# Sheet1.net
KiCad netlist of a schematic drawn in Altium Designer
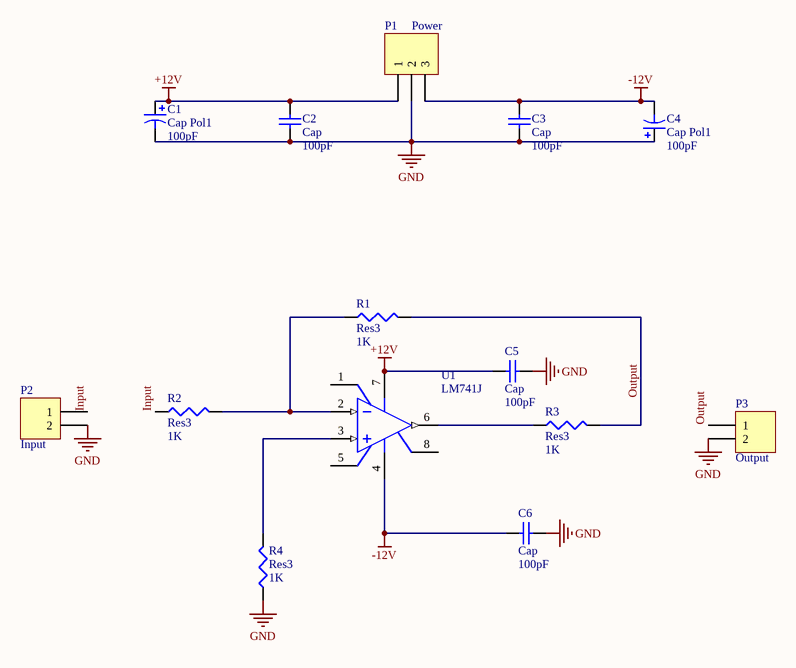
[diagram p0: Sheet1.SchDoc]

(export (version "E")
  (design (tool "Eeschema 10.0.6"))
  (components
    (comp (ref "C1")
      (value "Cap Pol1")
      (footprint "CAPR5-4X5")
      (description "Polarized Capacitor (Radial)")
      (fields (field (name "ALTIUM_VALUE") "100pF") (field (name "PUBLISHER") "Altium Limited"))
      (libsource (lib "Miscellaneous Devices") (part "Cap Pol1"))
    )
    (comp (ref "C2")
      (value "Cap")
      (footprint "CAPR5-4X5")
      (description "Capacitor")
      (fields (field (name "ALTIUM_VALUE") "100pF") (field (name "PUBLISHER") "Altium Limited"))
      (libsource (lib "Miscellaneous Devices") (part "Cap"))
    )
    (comp (ref "C3")
      (value "Cap")
      (footprint "CAPR5-4X5")
      (description "Capacitor")
      (fields (field (name "ALTIUM_VALUE") "100pF") (field (name "PUBLISHER") "Altium Limited"))
      (libsource (lib "Miscellaneous Devices") (part "Cap"))
    )
    (comp (ref "C4")
      (value "Cap Pol1")
      (footprint "CAPR5-4X5")
      (description "Polarized Capacitor (Radial)")
      (fields (field (name "ALTIUM_VALUE") "100pF") (field (name "PUBLISHER") "Altium Limited"))
      (libsource (lib "Miscellaneous Devices") (part "Cap Pol1"))
    )
    (comp (ref "C5")
      (value "Cap")
      (footprint "CAPR5-4X5")
      (description "Capacitor")
      (fields (field (name "ALTIUM_VALUE") "100pF") (field (name "PUBLISHER") "Altium Limited"))
      (libsource (lib "Miscellaneous Devices") (part "Cap"))
    )
    (comp (ref "C6")
      (value "Cap")
      (footprint "CAPR5-4X5")
      (description "Capacitor")
      (fields (field (name "ALTIUM_VALUE") "100pF") (field (name "PUBLISHER") "Altium Limited"))
      (libsource (lib "Miscellaneous Devices") (part "Cap"))
    )
    (comp (ref "P1")
      (value "Power")
      (footprint "HDR1X3")
      (description "Header, 3-Pin")
      (fields (field (name "PUBLISHER") "Altium Limited"))
      (libsource (lib "Miscellaneous Connectors") (part "Header 3"))
    )
    (comp (ref "P2")
      (value "Input")
      (footprint "HDR1X2H")
      (description "Header, 2-Pin, Right Angle")
      (fields (field (name "PUBLISHER") "Altium Limited"))
      (libsource (lib "Miscellaneous Connectors") (part "Header 2H"))
    )
    (comp (ref "P3")
      (value "Output")
      (footprint "HDR1X2")
      (description "Header, 2-Pin")
      (fields (field (name "PUBLISHER") "Altium Limited"))
      (libsource (lib "Miscellaneous Connectors") (part "Header 2"))
    )
    (comp (ref "R1")
      (value "Res3")
      (footprint "J1-0603")
      (description "Resistor")
      (fields (field (name "ALTIUM_VALUE") "1K") (field (name "PUBLISHER") "Altium Limited"))
      (libsource (lib "Miscellaneous Devices") (part "Res3"))
    )
    (comp (ref "R2")
      (value "Res3")
      (footprint "J1-0603")
      (description "Resistor")
      (fields (field (name "ALTIUM_VALUE") "1K") (field (name "PUBLISHER") "Altium Limited"))
      (libsource (lib "Miscellaneous Devices") (part "Res3"))
    )
    (comp (ref "R3")
      (value "Res3")
      (footprint "J1-0603")
      (description "Resistor")
      (fields (field (name "ALTIUM_VALUE") "1K") (field (name "PUBLISHER") "Altium Limited"))
      (libsource (lib "Miscellaneous Devices") (part "Res3"))
    )
    (comp (ref "R4")
      (value "Res3")
      (footprint "J1-0603")
      (description "Resistor")
      (fields (field (name "ALTIUM_VALUE") "1K") (field (name "PUBLISHER") "Altium Limited"))
      (libsource (lib "Miscellaneous Devices") (part "Res3"))
    )
    (comp (ref "U1")
      (value "LM741J")
      (footprint "J08A")
      (description "Operational Amplifier, 8-pin CerDIP")
      (fields (field (name "MANUFACTURER") "National Semiconductor"))
      (libsource (lib "National Semiconductor Amplifier") (part "LM741J"))
    )
  )
  (nets
    (net (code "1") (name "+12V") (class "Default")
      (node (ref "C1") (pin "1") (pinfunction "1_1") (pintype "passive"))
      (node (ref "C2") (pin "2") (pinfunction "2_2") (pintype "passive"))
      (node (ref "C5") (pin "1") (pinfunction "1_1") (pintype "passive"))
      (node (ref "P1") (pin "1") (pinfunction "1_1") (pintype "passive"))
      (node (ref "U1") (pin "7") (pinfunction "V+_7") (pintype "power_in"))
    )
    (net (code "2") (name "-12V") (class "Default")
      (node (ref "C3") (pin "2") (pinfunction "2_2") (pintype "passive"))
      (node (ref "C4") (pin "2") (pinfunction "2_2") (pintype "passive"))
      (node (ref "C6") (pin "1") (pinfunction "1_1") (pintype "passive"))
      (node (ref "P1") (pin "3") (pinfunction "3_3") (pintype "passive"))
      (node (ref "U1") (pin "4") (pinfunction "V-_4") (pintype "power_in"))
    )
    (net (code "3") (name "/Input") (class "Default")
      (node (ref "P2") (pin "1") (pinfunction "1_1") (pintype "passive"))
      (node (ref "R2") (pin "1") (pinfunction "1_1") (pintype "passive"))
    )
    (net (code "4") (name "/Output") (class "Default")
      (node (ref "P3") (pin "1") (pinfunction "1_1") (pintype "passive"))
      (node (ref "R1") (pin "2") (pinfunction "2_2") (pintype "passive"))
      (node (ref "R3") (pin "2") (pinfunction "2_2") (pintype "passive"))
    )
    (net (code "5") (name "GND") (class "Default")
      (node (ref "C1") (pin "2") (pinfunction "2_2") (pintype "passive"))
      (node (ref "C2") (pin "1") (pinfunction "1_1") (pintype "passive"))
      (node (ref "C3") (pin "1") (pinfunction "1_1") (pintype "passive"))
      (node (ref "C4") (pin "1") (pinfunction "1_1") (pintype "passive"))
      (node (ref "C5") (pin "2") (pinfunction "2_2") (pintype "passive"))
      (node (ref "C6") (pin "2") (pinfunction "2_2") (pintype "passive"))
      (node (ref "P1") (pin "2") (pinfunction "2_2") (pintype "passive"))
      (node (ref "P2") (pin "2") (pinfunction "2_2") (pintype "passive"))
      (node (ref "P3") (pin "2") (pinfunction "2_2") (pintype "passive"))
      (node (ref "R4") (pin "1") (pinfunction "1_1") (pintype "passive"))
    )
    (net (code "6") (name "Net-(U1-IN+)") (class "Default")
      (node (ref "R4") (pin "2") (pinfunction "2_2") (pintype "passive"))
      (node (ref "U1") (pin "3") (pinfunction "IN+_3") (pintype "input"))
    )
    (net (code "7") (name "Net-(U1-IN-)") (class "Default")
      (node (ref "R1") (pin "1") (pinfunction "1_1") (pintype "passive"))
      (node (ref "R2") (pin "2") (pinfunction "2_2") (pintype "passive"))
      (node (ref "U1") (pin "2") (pinfunction "IN-_2") (pintype "input"))
    )
    (net (code "8") (name "Net-(U1-OUT)") (class "Default")
      (node (ref "R3") (pin "1") (pinfunction "1_1") (pintype "passive"))
      (node (ref "U1") (pin "6") (pinfunction "OUT_6") (pintype "output"))
    )
    (net (code "9") (name "unconnected-(U1-NC-Pad8)") (class "Default")
      (node (ref "U1") (pin "8") (pinfunction "NC_8") (pintype "passive"))
    )
    (net (code "10") (name "unconnected-(U1-OFS_NULL-Pad1)") (class "Default")
      (node (ref "U1") (pin "1") (pinfunction "OFS_NULL_1") (pintype "passive"))
    )
    (net (code "11") (name "unconnected-(U1-OFS_NULL-Pad5)") (class "Default")
      (node (ref "U1") (pin "5") (pinfunction "OFS_NULL_5") (pintype "passive"))
    )
  )
)
